# pnode.net
KiCad netlist of a schematic drawn in EAGLE
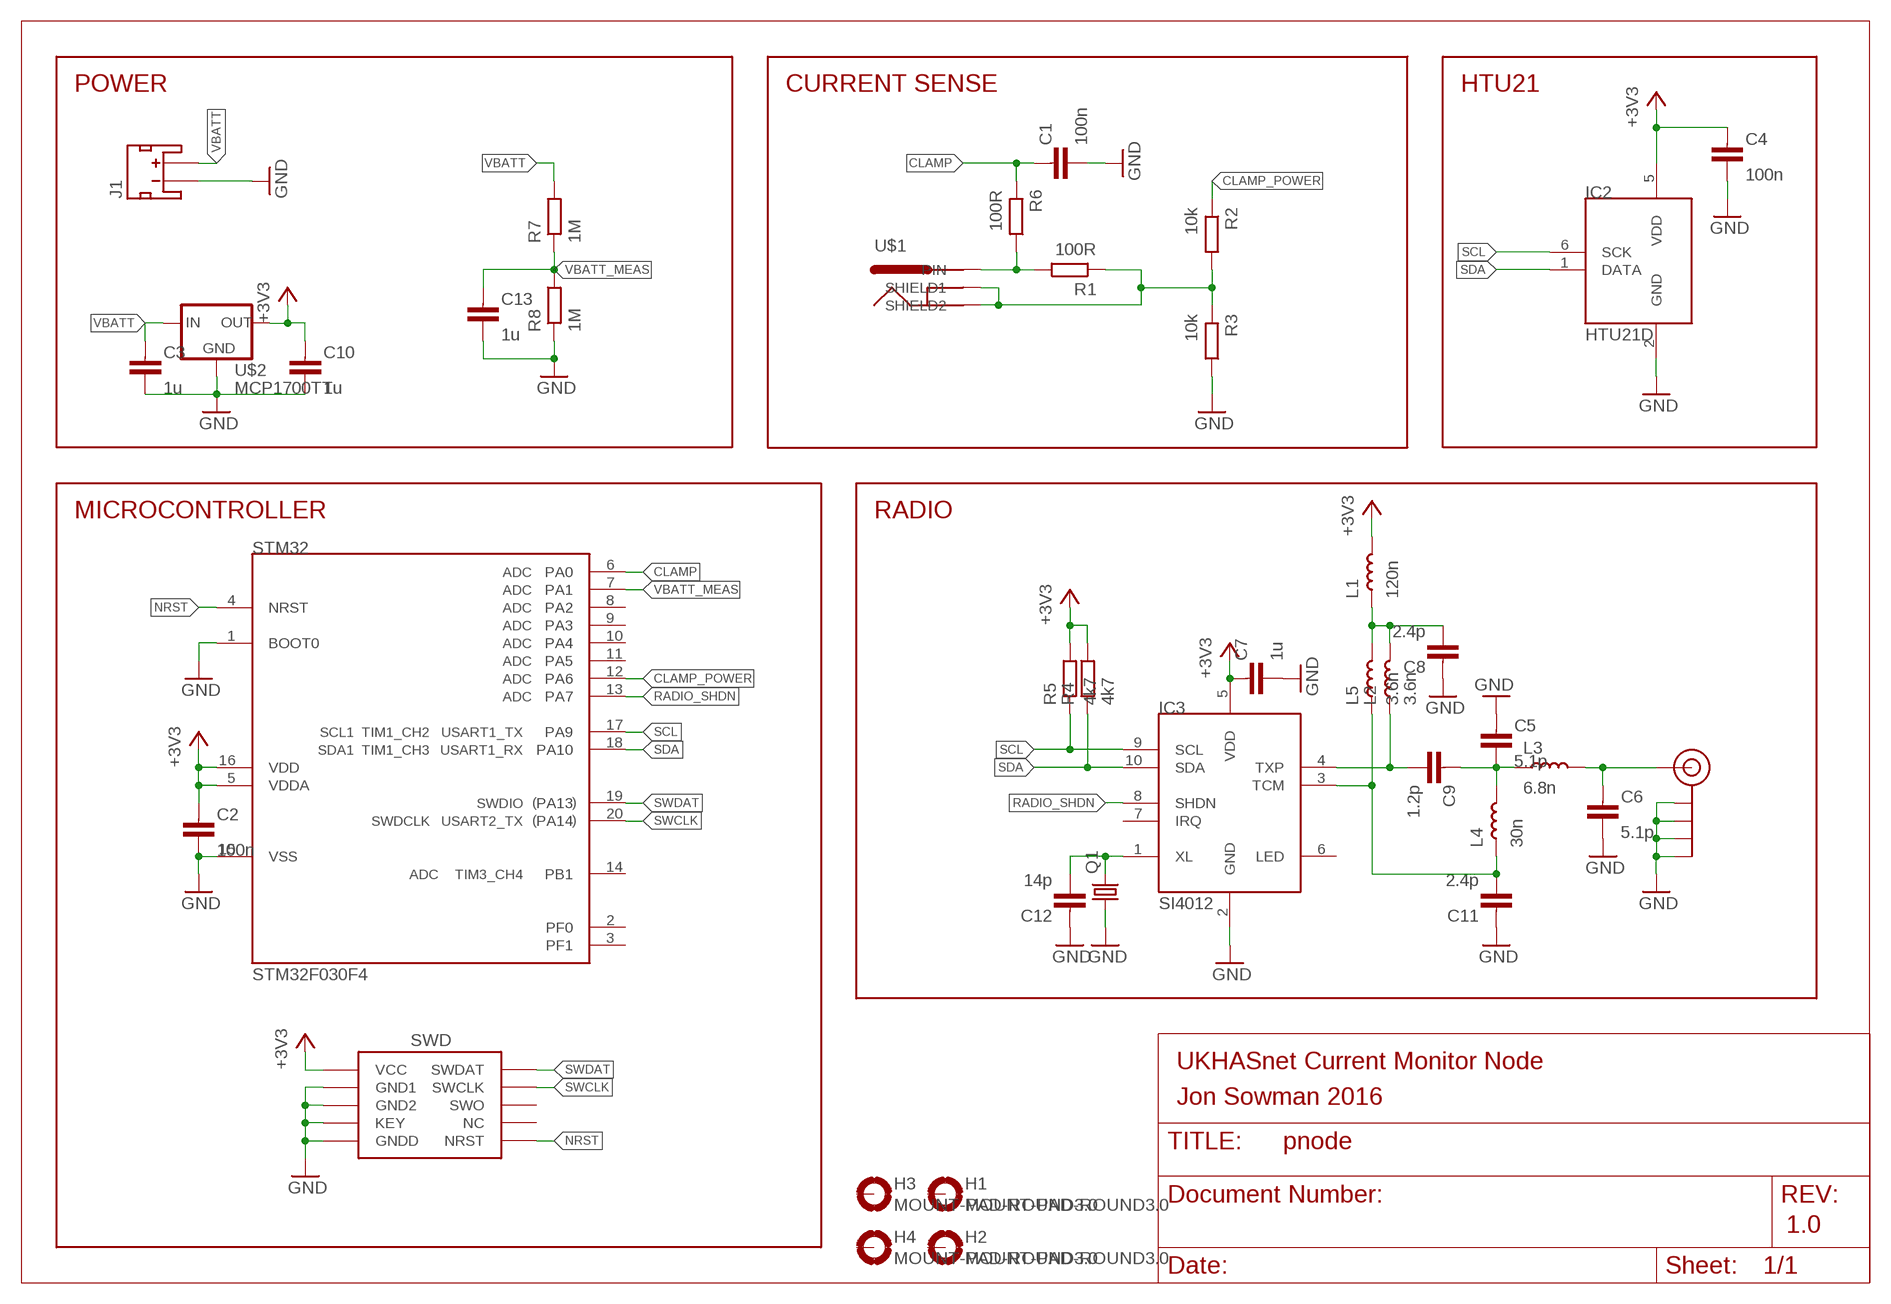
[diagram p0: schematic, sheet 1]

(export (version "E")
  (design (tool "Eeschema 10.0.6"))
  (components
    (comp (ref "C1")
      (value "100n")
      (footprint "eagle-import:C0603-N")
      (libsource (lib "eagle-import") (part "CAPACITOR0603-N"))
    )
    (comp (ref "C2")
      (value "100n")
      (footprint "eagle-import:C0603-N")
      (libsource (lib "eagle-import") (part "CAPACITOR0603-N"))
    )
    (comp (ref "C3")
      (value "1u")
      (footprint "eagle-import:C0603-N")
      (libsource (lib "eagle-import") (part "CAPACITOR0603-N"))
    )
    (comp (ref "C4")
      (value "100n")
      (footprint "eagle-import:C0603-N")
      (libsource (lib "eagle-import") (part "CAPACITOR0603-N"))
    )
    (comp (ref "C5")
      (value "5.1p")
      (footprint "eagle-import:C0603-N")
      (libsource (lib "eagle-import") (part "CAPACITOR0603-N"))
    )
    (comp (ref "C6")
      (value "5.1p")
      (footprint "eagle-import:C0603-N")
      (libsource (lib "eagle-import") (part "CAPACITOR0603-N"))
    )
    (comp (ref "C7")
      (value "1u")
      (footprint "eagle-import:C0603-N")
      (libsource (lib "eagle-import") (part "CAPACITOR0603-N"))
    )
    (comp (ref "C8")
      (value "2.4p")
      (footprint "eagle-import:C0603-N")
      (libsource (lib "eagle-import") (part "CAPACITOR0603-N"))
    )
    (comp (ref "C9")
      (value "1.2p")
      (footprint "eagle-import:C0603-N")
      (libsource (lib "eagle-import") (part "CAPACITOR0603-N"))
    )
    (comp (ref "C10")
      (value "1u")
      (footprint "eagle-import:C0603-N")
      (libsource (lib "eagle-import") (part "CAPACITOR0603-N"))
    )
    (comp (ref "C11")
      (value "2.4p")
      (footprint "eagle-import:C0603-N")
      (libsource (lib "eagle-import") (part "CAPACITOR0603-N"))
    )
    (comp (ref "C12")
      (value "14p")
      (footprint "eagle-import:C0603-N")
      (libsource (lib "eagle-import") (part "CAPACITOR0603-N"))
    )
    (comp (ref "C13")
      (value "1u")
      (footprint "eagle-import:C0603-N")
      (libsource (lib "eagle-import") (part "CAPACITOR0603-N"))
    )
    (comp (ref "H1")
      (value "MOUNT-PAD-ROUND3.0")
      (footprint "eagle-import:3,0-PAD")
      (libsource (lib "eagle-import") (part "MOUNT-PAD-ROUND3.0"))
    )
    (comp (ref "H2")
      (value "MOUNT-PAD-ROUND3.0")
      (footprint "eagle-import:3,0-PAD")
      (libsource (lib "eagle-import") (part "MOUNT-PAD-ROUND3.0"))
    )
    (comp (ref "H3")
      (value "MOUNT-PAD-ROUND3.0")
      (footprint "eagle-import:3,0-PAD")
      (libsource (lib "eagle-import") (part "MOUNT-PAD-ROUND3.0"))
    )
    (comp (ref "H4")
      (value "MOUNT-PAD-ROUND3.0")
      (footprint "eagle-import:3,0-PAD")
      (libsource (lib "eagle-import") (part "MOUNT-PAD-ROUND3.0"))
    )
    (comp (ref "IC2")
      (value "HTU21D")
      (footprint "eagle-import:DFN6-L")
      (libsource (lib "eagle-import") (part "HTU21D"))
    )
    (comp (ref "IC3")
      (value "SI4012")
      (footprint "eagle-import:MSOP10")
      (libsource (lib "eagle-import") (part "SI4012"))
    )
    (comp (ref "J$1")
      (value "SMA_EDGE")
      (footprint "eagle-import:SMA-EDGE")
      (libsource (lib "eagle-import") (part "SMA_EDGE"))
    )
    (comp (ref "J1")
      (value "JST_2MM_MALE_TH")
      (footprint "eagle-import:JST-2-TH")
      (libsource (lib "eagle-import") (part "JST_2MM_MALE_TH"))
    )
    (comp (ref "L1")
      (value "120n")
      (footprint "eagle-import:L0603-N")
      (libsource (lib "eagle-import") (part "INDUCTOR0603-N"))
    )
    (comp (ref "L2")
      (value "3.6n")
      (footprint "eagle-import:L0402-N")
      (libsource (lib "eagle-import") (part "INDUCTOR0402-N"))
    )
    (comp (ref "L3")
      (value "6.8n")
      (footprint "eagle-import:L0402-N")
      (libsource (lib "eagle-import") (part "INDUCTOR0402-N"))
    )
    (comp (ref "L4")
      (value "30n")
      (footprint "eagle-import:L0402-N")
      (libsource (lib "eagle-import") (part "INDUCTOR0402-N"))
    )
    (comp (ref "L5")
      (value "3.6n")
      (footprint "eagle-import:L0402-N")
      (libsource (lib "eagle-import") (part "INDUCTOR0402-N"))
    )
    (comp (ref "Q1")
      (value "CRYSTALHC49S")
      (footprint "eagle-import:HC49_S")
      (libsource (lib "eagle-import") (part "CRYSTALHC49S"))
    )
    (comp (ref "R1")
      (value "100R")
      (footprint "eagle-import:R0603-N")
      (libsource (lib "eagle-import") (part "RESISTOR0603-N"))
    )
    (comp (ref "R2")
      (value "10k")
      (footprint "eagle-import:R0603-N")
      (libsource (lib "eagle-import") (part "RESISTOR0603-N"))
    )
    (comp (ref "R3")
      (value "10k")
      (footprint "eagle-import:R0603-N")
      (libsource (lib "eagle-import") (part "RESISTOR0603-N"))
    )
    (comp (ref "R4")
      (value "4k7")
      (footprint "eagle-import:R0603-N")
      (libsource (lib "eagle-import") (part "RESISTOR0603-N"))
    )
    (comp (ref "R5")
      (value "4k7")
      (footprint "eagle-import:R0603-N")
      (libsource (lib "eagle-import") (part "RESISTOR0603-N"))
    )
    (comp (ref "R6")
      (value "100R")
      (footprint "eagle-import:R0603-N")
      (libsource (lib "eagle-import") (part "RESISTOR0603-N"))
    )
    (comp (ref "R7")
      (value "1M")
      (footprint "eagle-import:R0603-N")
      (libsource (lib "eagle-import") (part "RESISTOR0603-N"))
    )
    (comp (ref "R8")
      (value "1M")
      (footprint "eagle-import:R0603-N")
      (libsource (lib "eagle-import") (part "RESISTOR0603-N"))
    )
    (comp (ref "STM32")
      (value "STM32F030F4")
      (footprint "eagle-import:TSSOP20")
      (libsource (lib "eagle-import") (part "STM32F030F4"))
    )
    (comp (ref "U$1")
      (value "13MM_DC_JACKPTH")
      (footprint "eagle-import:13MM_DC_JACK")
      (libsource (lib "eagle-import") (part "13MM_DC_JACKPTH"))
    )
    (comp (ref "U$2")
      (value "MCP1700TT")
      (footprint "eagle-import:SOT23")
      (libsource (lib "eagle-import") (part "MCP1700TT"))
    )
    (comp (ref "U$3")
      (value "SWD_PTH_SHROUD")
      (footprint "eagle-import:SWD_PTH_SHROUD")
      (libsource (lib "eagle-import") (part "SWD_PTH_SHROUD"))
    )
  )
  (nets
    (net (code "1") (name "+3V3") (class "Default")
      (node (ref "C10") (pin "1") (pinfunction "1_1") (pintype "passive"))
      (node (ref "C2") (pin "1") (pinfunction "1_1") (pintype "passive"))
      (node (ref "C4") (pin "1") (pinfunction "1_1") (pintype "passive"))
      (node (ref "C7") (pin "1") (pinfunction "1_1") (pintype "passive"))
      (node (ref "IC2") (pin "5") (pinfunction "VDD_5") (pintype "power_in"))
      (node (ref "IC3") (pin "5") (pinfunction "VDD_5") (pintype "power_in"))
      (node (ref "L1") (pin "2") (pinfunction "P$2_2") (pintype "passive"))
      (node (ref "R4") (pin "2") (pinfunction "P$2_2") (pintype "passive"))
      (node (ref "R5") (pin "2") (pinfunction "P$2_2") (pintype "passive"))
      (node (ref "STM32") (pin "16") (pinfunction "VDD_16") (pintype "power_in"))
      (node (ref "STM32") (pin "5") (pinfunction "VDDA_5") (pintype "power_in"))
      (node (ref "U$2") (pin "2") (pinfunction "OUT_2") (pintype "passive"))
      (node (ref "U$3") (pin "1") (pinfunction "VCC_1") (pintype "power_in"))
    )
    (net (code "2") (name "CLAMP") (class "Default")
      (node (ref "C1") (pin "1") (pinfunction "1_1") (pintype "passive"))
      (node (ref "R6") (pin "1") (pinfunction "P$1_1") (pintype "passive"))
      (node (ref "STM32") (pin "6") (pinfunction "PA0_6") (pintype "bidirectional"))
    )
    (net (code "3") (name "CLAMP_POWER") (class "Default")
      (node (ref "R2") (pin "1") (pinfunction "P$1_1") (pintype "passive"))
      (node (ref "STM32") (pin "12") (pinfunction "PA6_12") (pintype "bidirectional"))
    )
    (net (code "4") (name "GND") (class "Default")
      (node (ref "C1") (pin "2") (pinfunction "2_2") (pintype "passive"))
      (node (ref "C10") (pin "2") (pinfunction "2_2") (pintype "passive"))
      (node (ref "C11") (pin "1") (pinfunction "1_1") (pintype "passive"))
      (node (ref "C12") (pin "1") (pinfunction "1_1") (pintype "passive"))
      (node (ref "C13") (pin "2") (pinfunction "2_2") (pintype "passive"))
      (node (ref "C2") (pin "2") (pinfunction "2_2") (pintype "passive"))
      (node (ref "C3") (pin "2") (pinfunction "2_2") (pintype "passive"))
      (node (ref "C4") (pin "2") (pinfunction "2_2") (pintype "passive"))
      (node (ref "C5") (pin "1") (pinfunction "1_1") (pintype "passive"))
      (node (ref "C6") (pin "2") (pinfunction "2_2") (pintype "passive"))
      (node (ref "C7") (pin "2") (pinfunction "2_2") (pintype "passive"))
      (node (ref "C8") (pin "1") (pinfunction "1_1") (pintype "passive"))
      (node (ref "IC2") (pin "2") (pinfunction "GND_2") (pintype "power_in"))
      (node (ref "IC3") (pin "2") (pinfunction "GND_2") (pintype "power_in"))
      (node (ref "J$1") (pin "GND@0") (pinfunction "GND_GND@0") (pintype "bidirectional"))
      (node (ref "J$1") (pin "GND@1") (pinfunction "GND_GND@1") (pintype "bidirectional"))
      (node (ref "J$1") (pin "GND@2") (pinfunction "GND_GND@2") (pintype "bidirectional"))
      (node (ref "J$1") (pin "GND@3") (pinfunction "GND_GND@3") (pintype "bidirectional"))
      (node (ref "J1") (pin "2") (pinfunction "-_2") (pintype "bidirectional"))
      (node (ref "Q1") (pin "1") (pinfunction "1_1") (pintype "passive"))
      (node (ref "R3") (pin "2") (pinfunction "P$2_2") (pintype "passive"))
      (node (ref "R8") (pin "1") (pinfunction "P$1_1") (pintype "passive"))
      (node (ref "STM32") (pin "1") (pinfunction "BOOT0_1") (pintype "input"))
      (node (ref "STM32") (pin "15") (pinfunction "VSS_15") (pintype "power_in"))
      (node (ref "U$2") (pin "1") (pinfunction "GND_1") (pintype "input"))
      (node (ref "U$3") (pin "3") (pinfunction "GND1_3") (pintype "power_in"))
      (node (ref "U$3") (pin "5") (pinfunction "GND2_5") (pintype "power_in"))
      (node (ref "U$3") (pin "7") (pinfunction "KEY_7") (pintype "bidirectional"))
      (node (ref "U$3") (pin "9") (pinfunction "GNDD_9") (pintype "power_in"))
    )
    (net (code "5") (name "NRST") (class "Default")
      (node (ref "STM32") (pin "4") (pinfunction "NRST_4") (pintype "input"))
      (node (ref "U$3") (pin "10") (pinfunction "NRST_10") (pintype "bidirectional"))
    )
    (net (code "6") (name "Net-(IC3-TCM)") (class "Default")
      (node (ref "C11") (pin "2") (pinfunction "2_2") (pintype "passive"))
      (node (ref "IC3") (pin "3") (pinfunction "TCM_3") (pintype "output"))
      (node (ref "L4") (pin "1") (pinfunction "P$1_1") (pintype "passive"))
      (node (ref "L5") (pin "1") (pinfunction "P$1_1") (pintype "passive"))
    )
    (net (code "7") (name "Net-(IC3-TXP)") (class "Default")
      (node (ref "C9") (pin "2") (pinfunction "2_2") (pintype "passive"))
      (node (ref "IC3") (pin "4") (pinfunction "TXP_4") (pintype "output"))
      (node (ref "L2") (pin "1") (pinfunction "P$1_1") (pintype "passive"))
    )
    (net (code "8") (name "Net-(IC3-XL)") (class "Default")
      (node (ref "C12") (pin "2") (pinfunction "2_2") (pintype "passive"))
      (node (ref "IC3") (pin "1") (pinfunction "XL_1") (pintype "bidirectional"))
      (node (ref "Q1") (pin "2") (pinfunction "2_2") (pintype "passive"))
    )
    (net (code "9") (name "Net-(J$1-SIGNAL)") (class "Default")
      (node (ref "C6") (pin "1") (pinfunction "1_1") (pintype "passive"))
      (node (ref "J$1") (pin "SIG") (pinfunction "SIGNAL_SIG") (pintype "bidirectional"))
      (node (ref "L3") (pin "2") (pinfunction "P$2_2") (pintype "passive"))
    )
    (net (code "10") (name "Net-(L1-P$1)") (class "Default")
      (node (ref "C8") (pin "2") (pinfunction "2_2") (pintype "passive"))
      (node (ref "L1") (pin "1") (pinfunction "P$1_1") (pintype "passive"))
      (node (ref "L2") (pin "2") (pinfunction "P$2_2") (pintype "passive"))
      (node (ref "L5") (pin "2") (pinfunction "P$2_2") (pintype "passive"))
    )
    (net (code "11") (name "Net-(L3-P$1)") (class "Default")
      (node (ref "C5") (pin "2") (pinfunction "2_2") (pintype "passive"))
      (node (ref "C9") (pin "1") (pinfunction "1_1") (pintype "passive"))
      (node (ref "L3") (pin "1") (pinfunction "P$1_1") (pintype "passive"))
      (node (ref "L4") (pin "2") (pinfunction "P$2_2") (pintype "passive"))
    )
    (net (code "12") (name "Net-(R1-P$1)") (class "Default")
      (node (ref "R1") (pin "1") (pinfunction "P$1_1") (pintype "passive"))
      (node (ref "R2") (pin "2") (pinfunction "P$2_2") (pintype "passive"))
      (node (ref "R3") (pin "1") (pinfunction "P$1_1") (pintype "passive"))
      (node (ref "U$1") (pin "2") (pinfunction "SHIELD1_2") (pintype "bidirectional"))
      (node (ref "U$1") (pin "3") (pinfunction "SHIELD2_3") (pintype "bidirectional"))
    )
    (net (code "13") (name "Net-(R1-P$2)") (class "Default")
      (node (ref "R1") (pin "2") (pinfunction "P$2_2") (pintype "passive"))
      (node (ref "R6") (pin "2") (pinfunction "P$2_2") (pintype "passive"))
      (node (ref "U$1") (pin "1") (pinfunction "PIN_1") (pintype "bidirectional"))
    )
    (net (code "14") (name "RADIO_SHDN") (class "Default")
      (node (ref "IC3") (pin "8") (pinfunction "SHDN_8") (pintype "input"))
      (node (ref "STM32") (pin "13") (pinfunction "PA7_13") (pintype "bidirectional"))
    )
    (net (code "15") (name "SCL") (class "Default")
      (node (ref "IC2") (pin "6") (pinfunction "SCK_6") (pintype "input"))
      (node (ref "IC3") (pin "9") (pinfunction "SCL_9") (pintype "input"))
      (node (ref "R5") (pin "1") (pinfunction "P$1_1") (pintype "passive"))
      (node (ref "STM32") (pin "17") (pinfunction "PA9_17") (pintype "bidirectional"))
    )
    (net (code "16") (name "SDA") (class "Default")
      (node (ref "IC2") (pin "1") (pinfunction "DATA_1") (pintype "bidirectional"))
      (node (ref "IC3") (pin "10") (pinfunction "SDA_10") (pintype "bidirectional"))
      (node (ref "R4") (pin "1") (pinfunction "P$1_1") (pintype "passive"))
      (node (ref "STM32") (pin "18") (pinfunction "PA10_18") (pintype "bidirectional"))
    )
    (net (code "17") (name "SWCLK") (class "Default")
      (node (ref "STM32") (pin "20") (pinfunction "PA14_20") (pintype "bidirectional"))
      (node (ref "U$3") (pin "4") (pinfunction "SWCLK_4") (pintype "bidirectional"))
    )
    (net (code "18") (name "SWDAT") (class "Default")
      (node (ref "STM32") (pin "19") (pinfunction "PA13_19") (pintype "bidirectional"))
      (node (ref "U$3") (pin "2") (pinfunction "SWDAT_2") (pintype "bidirectional"))
    )
    (net (code "19") (name "VBATT") (class "Default")
      (node (ref "C3") (pin "1") (pinfunction "1_1") (pintype "passive"))
      (node (ref "J1") (pin "1") (pinfunction "+_1") (pintype "bidirectional"))
      (node (ref "R7") (pin "2") (pinfunction "P$2_2") (pintype "passive"))
      (node (ref "U$2") (pin "3") (pinfunction "IN_3") (pintype "input"))
    )
    (net (code "20") (name "VBATT_MEAS") (class "Default")
      (node (ref "C13") (pin "1") (pinfunction "1_1") (pintype "passive"))
      (node (ref "R7") (pin "1") (pinfunction "P$1_1") (pintype "passive"))
      (node (ref "R8") (pin "2") (pinfunction "P$2_2") (pintype "passive"))
      (node (ref "STM32") (pin "7") (pinfunction "PA1_7") (pintype "bidirectional"))
    )
    (net (code "21") (name "unconnected-(H1-MOUNT-PadB3,0)") (class "Default")
      (node (ref "H1") (pin "B3,0") (pinfunction "MOUNT_B3,0") (pintype "passive"))
    )
    (net (code "22") (name "unconnected-(H2-MOUNT-PadB3,0)") (class "Default")
      (node (ref "H2") (pin "B3,0") (pinfunction "MOUNT_B3,0") (pintype "passive"))
    )
    (net (code "23") (name "unconnected-(H3-MOUNT-PadB3,0)") (class "Default")
      (node (ref "H3") (pin "B3,0") (pinfunction "MOUNT_B3,0") (pintype "passive"))
    )
    (net (code "24") (name "unconnected-(H4-MOUNT-PadB3,0)") (class "Default")
      (node (ref "H4") (pin "B3,0") (pinfunction "MOUNT_B3,0") (pintype "passive"))
    )
    (net (code "25") (name "unconnected-(IC3-IRQ-Pad7)") (class "Default")
      (node (ref "IC3") (pin "7") (pinfunction "IRQ_7") (pintype "output"))
    )
    (net (code "26") (name "unconnected-(IC3-LED-Pad6)") (class "Default")
      (node (ref "IC3") (pin "6") (pinfunction "LED_6") (pintype "output"))
    )
    (net (code "27") (name "unconnected-(STM32-PA2-Pad8)") (class "Default")
      (node (ref "STM32") (pin "8") (pinfunction "PA2_8") (pintype "bidirectional"))
    )
    (net (code "28") (name "unconnected-(STM32-PA3-Pad9)") (class "Default")
      (node (ref "STM32") (pin "9") (pinfunction "PA3_9") (pintype "bidirectional"))
    )
    (net (code "29") (name "unconnected-(STM32-PA4-Pad10)") (class "Default")
      (node (ref "STM32") (pin "10") (pinfunction "PA4_10") (pintype "bidirectional"))
    )
    (net (code "30") (name "unconnected-(STM32-PA5-Pad11)") (class "Default")
      (node (ref "STM32") (pin "11") (pinfunction "PA5_11") (pintype "bidirectional"))
    )
    (net (code "31") (name "unconnected-(STM32-PB1-Pad14)") (class "Default")
      (node (ref "STM32") (pin "14") (pinfunction "PB1_14") (pintype "bidirectional"))
    )
    (net (code "32") (name "unconnected-(STM32-PF0-Pad2)") (class "Default")
      (node (ref "STM32") (pin "2") (pinfunction "PF0_2") (pintype "bidirectional"))
    )
    (net (code "33") (name "unconnected-(STM32-PF1-Pad3)") (class "Default")
      (node (ref "STM32") (pin "3") (pinfunction "PF1_3") (pintype "bidirectional"))
    )
    (net (code "34") (name "unconnected-(U$3-NC-Pad8)") (class "Default")
      (node (ref "U$3") (pin "8") (pinfunction "NC_8") (pintype "no_connect"))
    )
    (net (code "35") (name "unconnected-(U$3-SWO-Pad6)") (class "Default")
      (node (ref "U$3") (pin "6") (pinfunction "SWO_6") (pintype "bidirectional"))
    )
  )
)
